# 6V_Supply.net
KiCad netlist of a schematic drawn in Altium Designer
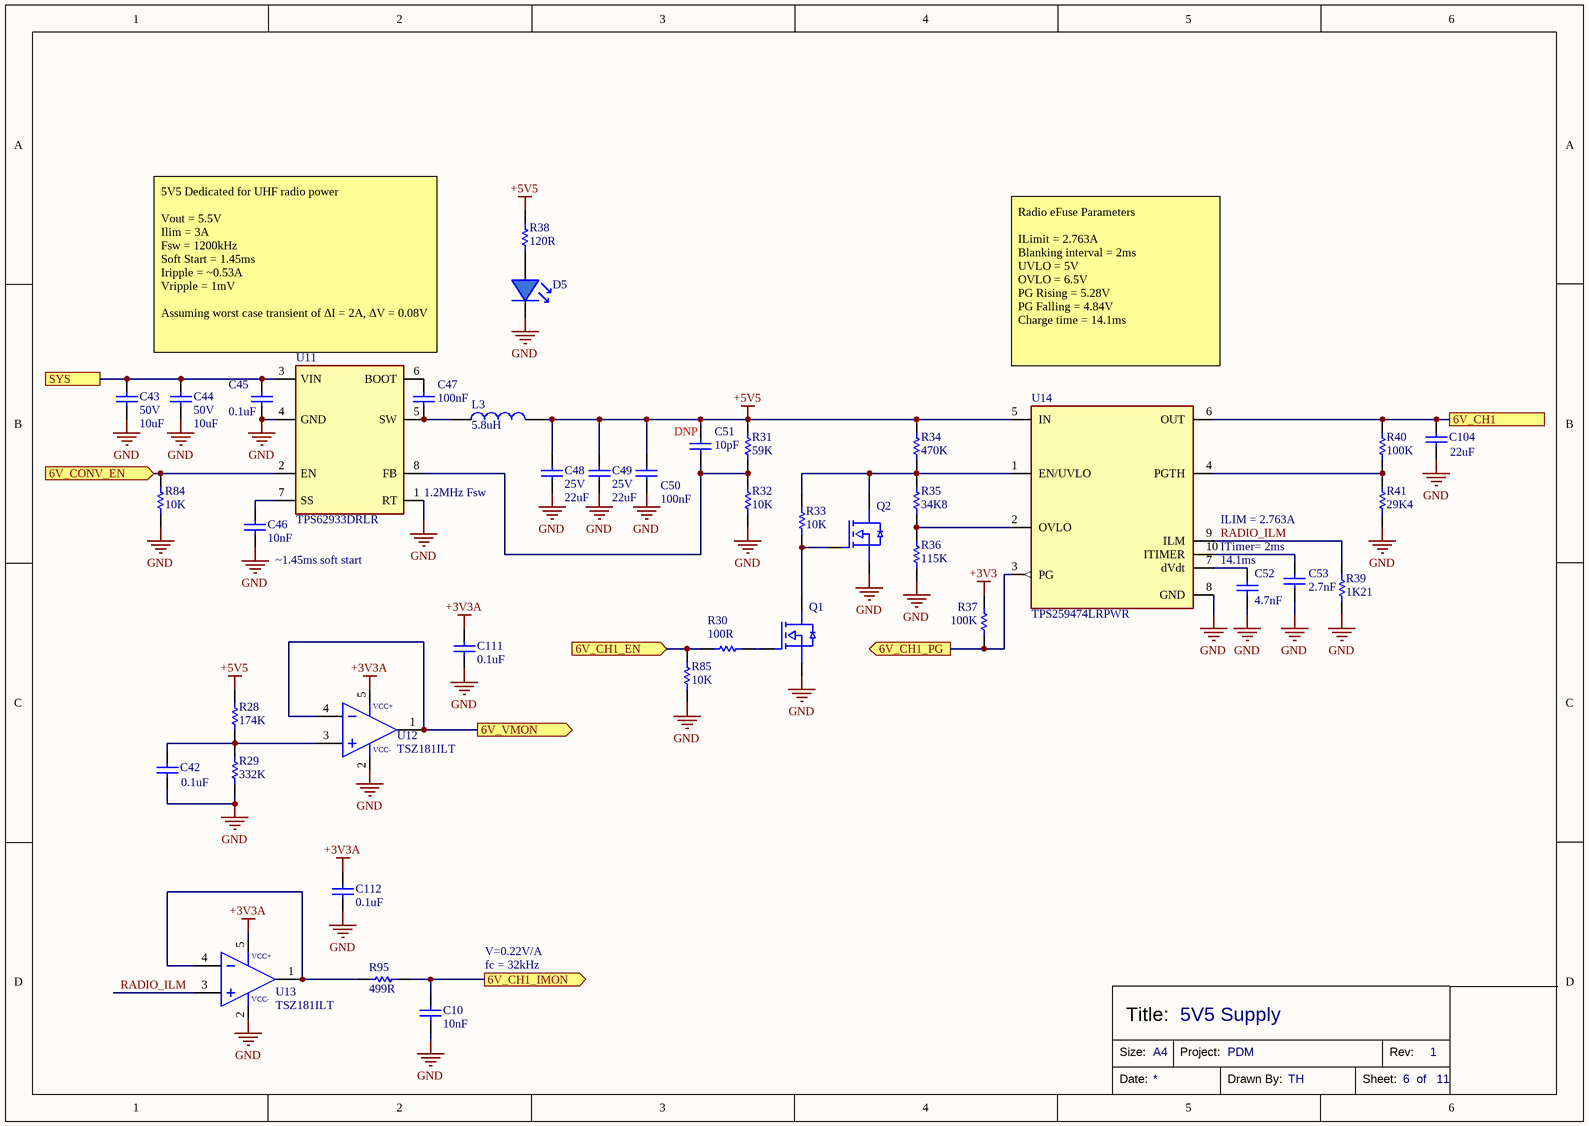
[diagram p0: 6V_Supply.SchDoc]

(export (version "E")
  (design (tool "Eeschema 10.0.6"))
  (components
    (comp (ref "C10")
      (value "CL21B103KBANNNC")
      (footprint "CAPC0805X060")
      (description "10nF ±10% 50V Ceramic Capacitor X7R 0805 (2012 Metric)")
      (fields
        (field (name "DISTRIBUTOR PART NUMBER") "1276-1015-1-ND")
        (field (name "TOLERANCE") "10%")
        (field (name "CAPACITANCE") "10nF")
      )
      (libsource (lib "Ahristi_Library") (part "CL21B103KBANNNC"))
    )
    (comp (ref "C42")
      (value "CL21B104KACNNNC")
      (footprint "CAPC0805X060")
      (description "0.1uF ±10% 25V Ceramic Capacitor X7R 0805 (2012 Metric)")
      (fields
        (field (name "DISTRIBUTOR PART NUMBER") "1276-1099-1-ND")
        (field (name "TOLERANCE") "10%")
        (field (name "CAPACITANCE") "0.1uF")
      )
      (libsource (lib "Ahristi_Library") (part "CL21B104KACNNNC"))
    )
    (comp (ref "C43")
      (value "CL32B106KBJNNNE")
      (footprint "CAPC1210X090")
      (description "10 µF ±10% 50V Ceramic Capacitor X7R 1210 (3225 Metric)")
      (fields
        (field (name "DISTRIBUTOR PART NUMBER") "1276-3387-1-ND")
        (field (name "TOLERANCE") "10%")
        (field (name "VOLTAGE RATING") "50V")
        (field (name "CAPACITANCE") "10uF")
      )
      (libsource (lib "Ahristi_Library") (part "CL32B106KBJNNNE"))
    )
    (comp (ref "C44")
      (value "CL32B106KBJNNNE")
      (footprint "CAPC1210X090")
      (description "10 µF ±10% 50V Ceramic Capacitor X7R 1210 (3225 Metric)")
      (fields
        (field (name "DISTRIBUTOR PART NUMBER") "1276-3387-1-ND")
        (field (name "TOLERANCE") "10%")
        (field (name "VOLTAGE RATING") "50V")
        (field (name "CAPACITANCE") "10uF")
      )
      (libsource (lib "Ahristi_Library") (part "CL32B106KBJNNNE"))
    )
    (comp (ref "C45")
      (value "CL05B104KB5NNNC")
      (footprint "CAPC0402X020")
      (description "0.1 µF ±10% 50V Ceramic Capacitor X7R 0402 (1005 Metric)")
      (fields
        (field (name "TOLERANCE") "10%")
        (field (name "DISTRIBUTOR PART NUMBER") "1276-CL05B104KB5NNNCCT-ND")
        (field (name "CAPACITANCE") "0.1uF")
      )
      (libsource (lib "Ahristi_Library") (part "CL05B104KB5NNNC"))
    )
    (comp (ref "C46")
      (value "CL21B103KBANNNC")
      (footprint "CAPC0805X060")
      (description "10nF ±10% 50V Ceramic Capacitor X7R 0805 (2012 Metric)")
      (fields
        (field (name "DISTRIBUTOR PART NUMBER") "1276-1015-1-ND")
        (field (name "TOLERANCE") "10%")
        (field (name "CAPACITANCE") "10nF")
      )
      (libsource (lib "Ahristi_Library") (part "CL21B103KBANNNC"))
    )
    (comp (ref "C47")
      (value "C0603C104K5RACTU")
      (footprint "CAPC0603X040")
      (description "0.1 µF ±10% 50V Ceramic Capacitor X7R 0603 (1608 Metric)")
      (fields
        (field (name "DISTRIBUTOR PART NUMBER") "399-C0603C104K5RACTUCT-ND")
        (field (name "TOLERANCE") "10%")
        (field (name "CAPACITANCE") "100nF")
      )
      (libsource (lib "Ahristi_Library") (part "C0603C104K5RACTU"))
    )
    (comp (ref "C48")
      (value "CL32B226KAJNNNE")
      (footprint "CAPC1210X090")
      (description "22 µF ±10% 25V Ceramic Capacitor X7R 1210 (3225 Metric)")
      (fields
        (field (name "DISTRIBUTOR PART NUMBER") "1276-3392-1-ND")
        (field (name "TOLERANCE") "10%")
        (field (name "VOLTAGE RATING") "25V")
        (field (name "CAPACITANCE") "22uF")
      )
      (libsource (lib "Ahristi_Library") (part "CL32B226KAJNNNE"))
    )
    (comp (ref "C49")
      (value "CL32B226KAJNNNE")
      (footprint "CAPC1210X090")
      (description "22 µF ±10% 25V Ceramic Capacitor X7R 1210 (3225 Metric)")
      (fields
        (field (name "DISTRIBUTOR PART NUMBER") "1276-3392-1-ND")
        (field (name "TOLERANCE") "10%")
        (field (name "VOLTAGE RATING") "25V")
        (field (name "CAPACITANCE") "22uF")
      )
      (libsource (lib "Ahristi_Library") (part "CL32B226KAJNNNE"))
    )
    (comp (ref "C50")
      (value "C0603C104K5RACTU")
      (footprint "CAPC0603X040")
      (description "0.1 µF ±10% 50V Ceramic Capacitor X7R 0603 (1608 Metric)")
      (fields
        (field (name "DISTRIBUTOR PART NUMBER") "399-C0603C104K5RACTUCT-ND")
        (field (name "TOLERANCE") "10%")
        (field (name "CAPACITANCE") "100nF")
      )
      (libsource (lib "Ahristi_Library") (part "C0603C104K5RACTU"))
    )
    (comp (ref "C51")
      (value "C0603C104K5RACTU")
      (footprint "CAPC0603X040")
      (description "10 pF ±5% 50V Ceramic Capacitor C0G, NP0 0603 (1608 Metric)")
      (fields
        (field (name "PART NUMBER") "C0603C100J5GACTU")
        (field (name "DISTRIBUTOR PART NUMBER") "399-C0603C100J5GACTUCT-ND")
        (field (name "CAPACITANCE") "10pF")
      )
      (libsource (lib "Ahristi_Library") (part "C0603C100J5GACTU"))
    )
    (comp (ref "C52")
      (value "CL21B105KAFNNNE")
      (footprint "CAPC0805X060")
      (description "4.7nF ±10% 50V Ceramic Capacitor X7R 0805 (2012 Metric)")
      (fields
        (field (name "PART NUMBER") "CL21B472KBANNNC")
        (field (name "DISTRIBUTOR PART NUMBER") "1276-1155-1-ND")
        (field (name "CAPACITANCE") "4.7nF")
      )
      (libsource (lib "Ahristi_Library") (part "CL21B472KBANNNC"))
    )
    (comp (ref "C53")
      (value "GRM2165C1H272JA01D")
      (footprint "CAPC0805X060")
      (description "2.7nF ±5% 50V Ceramic Capacitor C0G, NP0 0805 (2012 Metric)")
      (fields
        (field (name "DISTRIBUTOR PART NUMBER") "490-1630-1-ND")
        (field (name "TOLERANCE") "5%")
        (field (name "CAPACITANCE") "2.7nF")
      )
      (libsource (lib "Ahristi_Library") (part "GRM2165C1H272JA01D"))
    )
    (comp (ref "C104")
      (value "CL32B226MOJNNNE")
      (footprint "CAPC1210X090")
      (description "22 µF ±20% 16V Ceramic Capacitor X7R 1210 (3225 Metric)")
      (fields
        (field (name "DISTRIBUTOR PART NUMBER") "1276-3395-1-ND")
        (field (name "TOLERANCE") "10%")
        (field (name "CAPACITANCE") "22uF")
      )
      (libsource (lib "Ahristi_Library") (part "CL32B226MOJNNNE"))
    )
    (comp (ref "C111")
      (value "C0603C104K5RACTU")
      (footprint "CAPC0603X040")
      (description "0.1 µF ±10% 50V Ceramic Capacitor X7R 0603 (1608 Metric)")
      (fields
        (field (name "DISTRIBUTOR PART NUMBER") "399-C0603C104K5RACTUCT-ND")
        (field (name "TOLERANCE") "10%")
        (field (name "CAPACITANCE") "0.1uF")
      )
      (libsource (lib "Ahristi_Library") (part "C0603C104K5RACTU"))
    )
    (comp (ref "C112")
      (value "C0603C104K5RACTU")
      (footprint "CAPC0603X040")
      (description "0.1 µF ±10% 50V Ceramic Capacitor X7R 0603 (1608 Metric)")
      (fields
        (field (name "DISTRIBUTOR PART NUMBER") "399-C0603C104K5RACTUCT-ND")
        (field (name "TOLERANCE") "10%")
        (field (name "CAPACITANCE") "0.1uF")
      )
      (libsource (lib "Ahristi_Library") (part "C0603C104K5RACTU"))
    )
    (comp (ref "D5")
      (value "LSM0805463V")
      (footprint "LEDB_0805")
      (description "Blue 469nm LED Indication - Discrete 3V 0805 (2012 Metric)")
      (fields (field (name "DISTRIBUTOR PART NUMBER") "28-LSM0805463VCT-ND"))
      (libsource (lib "Ahristi_Library") (part "LEDB0805"))
    )
    (comp (ref "L3")
      (value "744316560")
      (footprint "744316560")
      (description "Inductor 5.6uH 4.5A Shielded 28.5mOhm SMD")
      (fields (field (name "DISTRIBUTOR PART NUMBER") "732-6183-1-ND"))
      (libsource (lib "Ahristi_Library") (part "744316560"))
    )
    (comp (ref "Q1")
      (value "T2N7002AK,LM")
      (footprint "SOT23-3 MOSFET")
      (description "N-Channel 60 V 200mA (Ta) 320mW (Ta) Surface Mount SOT-23-3")
      (fields (field (name "DISTRIBUTOR PART NUMBER") "T2N7002AKLMCT-ND"))
      (libsource (lib "Ahristi_Library") (part "T2N7002AK,LM"))
    )
    (comp (ref "Q2")
      (value "T2N7002AK,LM")
      (footprint "SOT23-3 MOSFET")
      (description "N-Channel 60 V 200mA (Ta) 320mW (Ta) Surface Mount SOT-23-3")
      (fields (field (name "DISTRIBUTOR PART NUMBER") "T2N7002AKLMCT-ND"))
      (libsource (lib "Ahristi_Library") (part "T2N7002AK,LM"))
    )
    (comp (ref "R28")
      (value "RMCF0603FT174K")
      (footprint "RESC0603")
      (description "174 kOhms ±1% 0.1W, 1/10W Chip Resistor 0603 (1608 Metric) Automotive AEC-Q200 Thick Film")
      (fields
        (field (name "TOLERANCE") "1%")
        (field (name "DISTRIBUTOR PART NUMBER") "RMCF0603FT174KCT-ND")
        (field (name "RESISTANCE") "174K")
      )
      (libsource (lib "Ahristi_Library") (part "RMCF0603FT174K"))
    )
    (comp (ref "R29")
      (value "RMCF0805FT332K")
      (footprint "RESC0805")
      (description "332 kOhms ±1% 0.125W, 1/8W Chip Resistor 0805 (2012 Metric) Automotive AEC-Q200 Thick Film")
      (fields
        (field (name "TOLERANCE") "1%")
        (field (name "DISTRIBUTOR PART NUMBER") "RMCF0805FT332KCT-ND")
        (field (name "RESISTANCE") "332K")
      )
      (libsource (lib "Ahristi_Library") (part "RMCF0805FT332K"))
    )
    (comp (ref "R30")
      (value "RMCF0805FT100R")
      (footprint "RESC0805")
      (description "100 Ohms ±1% 0.125W, 1/8W Chip Resistor 0805 (2012 Metric) Automotive AEC-Q200 Thick Film")
      (fields
        (field (name "TOLERANCE") "1%")
        (field (name "DISTRIBUTOR PART NUMBER") "RMCF0805FT100RCT-ND")
        (field (name "RESISTANCE") "100R")
      )
      (libsource (lib "Ahristi_Library") (part "RMCF0805FT100R"))
    )
    (comp (ref "R31")
      (value "RMCF0603FT59K0")
      (footprint "RESC0603")
      (description "59 kOhms ±1% 0.1W, 1/10W Chip Resistor 0603 (1608 Metric) Automotive AEC-Q200 Thick Film")
      (fields
        (field (name "TOLERANCE") "1%")
        (field (name "DISTRIBUTOR PART NUMBER") "RMCF0603FT59K0CT-ND")
        (field (name "RESISTANCE") "59K")
      )
      (libsource (lib "Ahristi_Library") (part "RMCF0603FT59K0"))
    )
    (comp (ref "R32")
      (value "RMCF0603FT10K0")
      (footprint "RESC0603")
      (description "10 kOhms ±1% 0.1W, 1/10W Chip Resistor 0603 (1608 Metric) Automotive AEC-Q200 Thick Film")
      (fields
        (field (name "TOLERANCE") "1%")
        (field (name "DISTRIBUTOR PART NUMBER") "RMCF0603FT10K0CT-ND")
        (field (name "RESISTANCE") "10K")
      )
      (libsource (lib "Ahristi_Library") (part "RMCF0603FT10K0"))
    )
    (comp (ref "R33")
      (value "RMCF0805FT10K0")
      (footprint "RESC0805")
      (description "10 kOhms ±1% 0.125W, 1/8W Chip Resistor 0805 (2012 Metric) Automotive AEC-Q200 Thick Film")
      (fields
        (field (name "TOLERANCE") "1%")
        (field (name "DISTRIBUTOR PART NUMBER") "RMCF0805FT10K0CT-ND")
        (field (name "RESISTANCE") "10K")
      )
      (libsource (lib "Ahristi_Library") (part "RMCF0805FT10K0"))
    )
    (comp (ref "R34")
      (value "RMCF0603FT470K")
      (footprint "RESC0603")
      (description "470 kOhms ±1% 0.1W, 1/10W Chip Resistor 0603 (1608 Metric) Automotive AEC-Q200 Thick Film")
      (fields
        (field (name "TOLERANCE") "1%")
        (field (name "DISTRIBUTOR PART NUMBER") "RMCF0603FT470KCT-ND")
        (field (name "RESISTANCE") "470K")
      )
      (libsource (lib "Ahristi_Library") (part "RMCF0603FT470K"))
    )
    (comp (ref "R35")
      (value "RMCF0805FT34K8")
      (footprint "RESC0805")
      (description "34.8 kOhms ±1% 0.125W, 1/8W Chip Resistor 0805 (2012 Metric) Automotive AEC-Q200 Thick Film")
      (fields
        (field (name "TOLERANCE") "1%")
        (field (name "DISTRIBUTOR PART NUMBER") "RMCF0805FT34K8CT-ND")
        (field (name "RESISTANCE") "34K8")
      )
      (libsource (lib "Ahristi_Library") (part "RMCF0805FT34K8"))
    )
    (comp (ref "R36")
      (value "RMCF0805FT115K")
      (footprint "RESC0805")
      (description "115 kOhms ±1% 0.125W, 1/8W Chip Resistor 0805 (2012 Metric) Automotive AEC-Q200 Thick Film")
      (fields
        (field (name "TOLERANCE") "1%")
        (field (name "DISTRIBUTOR PART NUMBER") "RMCF0805FT115KCT-ND")
        (field (name "RESISTANCE") "115K")
      )
      (libsource (lib "Ahristi_Library") (part "RMCF0805FT115K"))
    )
    (comp (ref "R37")
      (value "RMCF0805FG100K")
      (footprint "RESC0805")
      (description "100 kOhms ±1% 0.125W, 1/8W Chip Resistor 0805 (2012 Metric) Automotive AEC-Q200 Thick Film")
      (fields
        (field (name "TOLERANCE") "1%")
        (field (name "DISTRIBUTOR PART NUMBER") "RMCF0805FG100KCT-ND")
        (field (name "RESISTANCE") "100K")
      )
      (libsource (lib "Ahristi_Library") (part "RMCF0805FG100K"))
    )
    (comp (ref "R38")
      (value "RMCF0805FT120R")
      (footprint "RESC0805")
      (description "120 Ohms ±1% 0.125W, 1/8W Chip Resistor 0805 (2012 Metric) Automotive AEC-Q200 Thick Film")
      (fields
        (field (name "TOLERANCE") "1%")
        (field (name "DISTRIBUTOR PART NUMBER") "738-RMCF0805FT120RCT-ND")
        (field (name "RESISTANCE") "120R")
      )
      (libsource (lib "Ahristi_Library") (part "RMCF0805FT120R"))
    )
    (comp (ref "R39")
      (value "RMCF0805FT1K21")
      (footprint "RESC0805")
      (description "1.21 kOhms ±1% 0.125W, 1/8W Chip Resistor 0805 (2012 Metric) Automotive AEC-Q200 Thick Film")
      (fields
        (field (name "TOLERANCE") "1%")
        (field (name "DISTRIBUTOR PART NUMBER") "RMCF0805FT1K21CT-ND")
        (field (name "RESISTANCE") "1K21")
      )
      (libsource (lib "Ahristi_Library") (part "RMCF0805FT1K21"))
    )
    (comp (ref "R40")
      (value "RMCF0805FG100K")
      (footprint "RESC0805")
      (description "100 kOhms ±1% 0.125W, 1/8W Chip Resistor 0805 (2012 Metric) Automotive AEC-Q200 Thick Film")
      (fields
        (field (name "TOLERANCE") "1%")
        (field (name "DISTRIBUTOR PART NUMBER") "RMCF0805FG100KCT-ND")
        (field (name "RESISTANCE") "100K")
      )
      (libsource (lib "Ahristi_Library") (part "RMCF0805FG100K"))
    )
    (comp (ref "R41")
      (value "RMCF0805FT29K4")
      (footprint "RESC0805")
      (description "29.4 kOhms ±1% 0.125W, 1/8W Chip Resistor 0805 (2012 Metric) Automotive AEC-Q200 Thick Film")
      (fields
        (field (name "TOLERANCE") "1%")
        (field (name "DISTRIBUTOR PART NUMBER") "RMCF0805FT29K4CT-ND")
        (field (name "RESISTANCE") "29K4")
      )
      (libsource (lib "Ahristi_Library") (part "RMCF0805FT29K4"))
    )
    (comp (ref "R84")
      (value "RMCF0805FT10K0")
      (footprint "RESC0805")
      (description "10 kOhms ±1% 0.125W, 1/8W Chip Resistor 0805 (2012 Metric) Automotive AEC-Q200 Thick Film")
      (fields
        (field (name "TOLERANCE") "1%")
        (field (name "DISTRIBUTOR PART NUMBER") "RMCF0805FT10K0CT-ND")
        (field (name "RESISTANCE") "10K")
      )
      (libsource (lib "Ahristi_Library") (part "RMCF0805FT10K0"))
    )
    (comp (ref "R85")
      (value "RMCF0805FT10K0")
      (footprint "RESC0805")
      (description "10 kOhms ±1% 0.125W, 1/8W Chip Resistor 0805 (2012 Metric) Automotive AEC-Q200 Thick Film")
      (fields
        (field (name "TOLERANCE") "1%")
        (field (name "DISTRIBUTOR PART NUMBER") "RMCF0805FT10K0CT-ND")
        (field (name "RESISTANCE") "10K")
      )
      (libsource (lib "Ahristi_Library") (part "RMCF0805FT10K0"))
    )
    (comp (ref "R95")
      (value "RMCF0805FT499R")
      (footprint "RESC0805")
      (description "499 Ohms ±1% 0.125W, 1/8W Chip Resistor 0805 (2012 Metric) Automotive AEC-Q200 Thick Film")
      (fields
        (field (name "TOLERANCE") "1%")
        (field (name "DISTRIBUTOR PART NUMBER") "RMCF0805FT499RCT-ND")
        (field (name "RESISTANCE") "499R")
      )
      (libsource (lib "Ahristi_Library") (part "RMCF0805FT499R"))
    )
    (comp (ref "U11")
      (value "TPS62933DRLR")
      (footprint "SOT-583")
      (description "Buck Switching Regulator IC Positive Adjustable 0.8V 1 Output 3A SOT-583")
      (fields (field (name "DISTRIBUTOR PART NUMBER") "296-TPS62933DRLRCT-ND"))
      (libsource (lib "Ahristi_Library") (part "TPS62933DRLR"))
    )
    (comp (ref "U12")
      (value "TSZ181ILT")
      (footprint "SOT23-5 IC")
      (description "Operational Amplifier, General Purpose, 2.2V~5.5V")
      (fields (field (name "DISTRIBUTOR PART NUMBER") "497-18084-1-ND"))
      (libsource (lib "Ahristi_Library") (part "TSZ181ILT"))
    )
    (comp (ref "U13")
      (value "TSZ181ILT")
      (footprint "SOT23-5 IC")
      (description "Operational Amplifier, General Purpose, 2.2V~5.5V")
      (fields (field (name "DISTRIBUTOR PART NUMBER") "497-18084-1-ND"))
      (libsource (lib "Ahristi_Library") (part "TSZ181ILT"))
    )
    (comp (ref "U14")
      (value "TPS259474LRPWR")
      (footprint "VFQFN-10")
      (description "eFuse 5.5A, 2.7V~23V, 28mOhm, Reverse Current Blocking with Input Reverse Polarity Protection")
      (fields (field (name "DISTRIBUTOR PART NUMBER") "296-TPS259474LRPWRCT-ND"))
      (libsource (lib "Ahristi_Library") (part "TPS259474LRPWR"))
    )
  )
  (nets
    (net (code "1") (name "+3V3") (class "Default")
      (node (ref "R37") (pin "2") (pinfunction "2_2") (pintype "passive"))
    )
    (net (code "2") (name "+3V3A") (class "Default")
      (node (ref "C111") (pin "2") (pinfunction "2_2") (pintype "passive"))
      (node (ref "C112") (pin "2") (pinfunction "2_2") (pintype "passive"))
      (node (ref "U12") (pin "5") (pinfunction "VCC+_5") (pintype "power_in"))
      (node (ref "U13") (pin "5") (pinfunction "VCC+_5") (pintype "power_in"))
    )
    (net (code "3") (name "+5V5") (class "Default")
      (node (ref "C48") (pin "2") (pinfunction "2_2") (pintype "passive"))
      (node (ref "C49") (pin "2") (pinfunction "2_2") (pintype "passive"))
      (node (ref "C50") (pin "2") (pinfunction "2_2") (pintype "passive"))
      (node (ref "C51") (pin "2") (pinfunction "2_2") (pintype "passive"))
      (node (ref "L3") (pin "2") (pinfunction "2_2") (pintype "passive"))
      (node (ref "R28") (pin "2") (pinfunction "2_2") (pintype "passive"))
      (node (ref "R31") (pin "2") (pinfunction "2_2") (pintype "passive"))
      (node (ref "R34") (pin "2") (pinfunction "2_2") (pintype "passive"))
      (node (ref "R38") (pin "2") (pinfunction "2_2") (pintype "passive"))
      (node (ref "U14") (pin "5") (pinfunction "IN_5") (pintype "passive"))
    )
    (net (code "4") (name "/6V_CH1") (class "Default")
      (node (ref "C104") (pin "2") (pinfunction "2_2") (pintype "passive"))
      (node (ref "R40") (pin "2") (pinfunction "2_2") (pintype "passive"))
      (node (ref "U14") (pin "6") (pinfunction "OUT_6") (pintype "passive"))
    )
    (net (code "5") (name "/6V_CH1_EN") (class "Default")
      (node (ref "R30") (pin "2") (pinfunction "2_2") (pintype "passive"))
      (node (ref "R85") (pin "2") (pinfunction "2_2") (pintype "passive"))
    )
    (net (code "6") (name "/6V_CH1_IMON") (class "Default")
      (node (ref "C10") (pin "2") (pinfunction "2_2") (pintype "passive"))
      (node (ref "R95") (pin "2") (pinfunction "2_2") (pintype "passive"))
    )
    (net (code "7") (name "/6V_CH1_PG") (class "Default")
      (node (ref "R37") (pin "1") (pinfunction "1_1") (pintype "passive"))
      (node (ref "U14") (pin "3") (pinfunction "PG_3") (pintype "output"))
    )
    (net (code "8") (name "/6V_CONV_EN") (class "Default")
      (node (ref "R84") (pin "2") (pinfunction "2_2") (pintype "passive"))
      (node (ref "U11") (pin "2") (pinfunction "EN_2") (pintype "passive"))
    )
    (net (code "9") (name "/6V_VMON") (class "Default")
      (node (ref "U12") (pin "1") (pinfunction "OUT_1") (pintype "passive"))
      (node (ref "U12") (pin "4") (pinfunction "IN-_4") (pintype "passive"))
    )
    (net (code "10") (name "/RADIO_ILM") (class "Default")
      (node (ref "R39") (pin "2") (pinfunction "2_2") (pintype "passive"))
      (node (ref "U13") (pin "3") (pinfunction "IN+_3") (pintype "passive"))
      (node (ref "U14") (pin "9") (pinfunction "ILM_9") (pintype "passive"))
    )
    (net (code "11") (name "/SYS") (class "Default")
      (node (ref "C43") (pin "2") (pinfunction "2_2") (pintype "passive"))
      (node (ref "C44") (pin "2") (pinfunction "2_2") (pintype "passive"))
      (node (ref "C45") (pin "2") (pinfunction "2_2") (pintype "passive"))
      (node (ref "U11") (pin "3") (pinfunction "VIN_3") (pintype "passive"))
    )
    (net (code "12") (name "GND") (class "Default")
      (node (ref "C10") (pin "1") (pinfunction "1_1") (pintype "passive"))
      (node (ref "C104") (pin "1") (pinfunction "1_1") (pintype "passive"))
      (node (ref "C111") (pin "1") (pinfunction "1_1") (pintype "passive"))
      (node (ref "C112") (pin "1") (pinfunction "1_1") (pintype "passive"))
      (node (ref "C42") (pin "1") (pinfunction "1_1") (pintype "passive"))
      (node (ref "C43") (pin "1") (pinfunction "1_1") (pintype "passive"))
      (node (ref "C44") (pin "1") (pinfunction "1_1") (pintype "passive"))
      (node (ref "C45") (pin "1") (pinfunction "1_1") (pintype "passive"))
      (node (ref "C46") (pin "1") (pinfunction "1_1") (pintype "passive"))
      (node (ref "C48") (pin "1") (pinfunction "1_1") (pintype "passive"))
      (node (ref "C49") (pin "1") (pinfunction "1_1") (pintype "passive"))
      (node (ref "C50") (pin "1") (pinfunction "1_1") (pintype "passive"))
      (node (ref "C52") (pin "1") (pinfunction "1_1") (pintype "passive"))
      (node (ref "C53") (pin "1") (pinfunction "1_1") (pintype "passive"))
      (node (ref "D5") (pin "K") (pinfunction "K_K") (pintype "passive"))
      (node (ref "Q1") (pin "S") (pinfunction "S_S") (pintype "passive"))
      (node (ref "Q2") (pin "S") (pinfunction "S_S") (pintype "passive"))
      (node (ref "R29") (pin "1") (pinfunction "1_1") (pintype "passive"))
      (node (ref "R32") (pin "1") (pinfunction "1_1") (pintype "passive"))
      (node (ref "R36") (pin "1") (pinfunction "1_1") (pintype "passive"))
      (node (ref "R39") (pin "1") (pinfunction "1_1") (pintype "passive"))
      (node (ref "R41") (pin "1") (pinfunction "1_1") (pintype "passive"))
      (node (ref "R84") (pin "1") (pinfunction "1_1") (pintype "passive"))
      (node (ref "R85") (pin "1") (pinfunction "1_1") (pintype "passive"))
      (node (ref "U11") (pin "1") (pinfunction "RT_1") (pintype "passive"))
      (node (ref "U11") (pin "4") (pinfunction "GND_4") (pintype "passive"))
      (node (ref "U12") (pin "2") (pinfunction "VCC-_2") (pintype "power_in"))
      (node (ref "U13") (pin "2") (pinfunction "VCC-_2") (pintype "power_in"))
      (node (ref "U14") (pin "8") (pinfunction "GND_8") (pintype "passive"))
    )
    (net (code "13") (name "Net-(D5-PadA)") (class "Default")
      (node (ref "D5") (pin "A") (pinfunction "A_A") (pintype "passive"))
      (node (ref "R38") (pin "1") (pinfunction "1_1") (pintype "passive"))
    )
    (net (code "14") (name "Net-(Q1-PadD)") (class "Default")
      (node (ref "Q1") (pin "D") (pinfunction "D_D") (pintype "passive"))
      (node (ref "Q2") (pin "G") (pinfunction "G_G") (pintype "passive"))
      (node (ref "R33") (pin "1") (pinfunction "1_1") (pintype "passive"))
    )
    (net (code "15") (name "Net-(Q1-PadG)") (class "Default")
      (node (ref "Q1") (pin "G") (pinfunction "G_G") (pintype "passive"))
      (node (ref "R30") (pin "1") (pinfunction "1_1") (pintype "passive"))
    )
    (net (code "16") (name "Net-(U11-BOOT)") (class "Default")
      (node (ref "C47") (pin "2") (pinfunction "2_2") (pintype "passive"))
      (node (ref "U11") (pin "6") (pinfunction "BOOT_6") (pintype "passive"))
    )
    (net (code "17") (name "Net-(U11-FB)") (class "Default")
      (node (ref "C51") (pin "1") (pinfunction "1_1") (pintype "passive"))
      (node (ref "R31") (pin "1") (pinfunction "1_1") (pintype "passive"))
      (node (ref "R32") (pin "2") (pinfunction "2_2") (pintype "passive"))
      (node (ref "U11") (pin "8") (pinfunction "FB_8") (pintype "passive"))
    )
    (net (code "18") (name "Net-(U11-SS)") (class "Default")
      (node (ref "C46") (pin "2") (pinfunction "2_2") (pintype "passive"))
      (node (ref "U11") (pin "7") (pinfunction "SS_7") (pintype "passive"))
    )
    (net (code "19") (name "Net-(U11-SW)") (class "Default")
      (node (ref "C47") (pin "1") (pinfunction "1_1") (pintype "passive"))
      (node (ref "L3") (pin "1") (pinfunction "1_1") (pintype "passive"))
      (node (ref "U11") (pin "5") (pinfunction "SW_5") (pintype "passive"))
    )
    (net (code "20") (name "Net-(U12-IN+)") (class "Default")
      (node (ref "C42") (pin "2") (pinfunction "2_2") (pintype "passive"))
      (node (ref "R28") (pin "1") (pinfunction "1_1") (pintype "passive"))
      (node (ref "R29") (pin "2") (pinfunction "2_2") (pintype "passive"))
      (node (ref "U12") (pin "3") (pinfunction "IN+_3") (pintype "passive"))
    )
    (net (code "21") (name "Net-(U13-IN-)") (class "Default")
      (node (ref "R95") (pin "1") (pinfunction "1_1") (pintype "passive"))
      (node (ref "U13") (pin "1") (pinfunction "OUT_1") (pintype "passive"))
      (node (ref "U13") (pin "4") (pinfunction "IN-_4") (pintype "passive"))
    )
    (net (code "22") (name "Net-(U14-EN{slash}UVLO)") (class "Default")
      (node (ref "Q2") (pin "D") (pinfunction "D_D") (pintype "passive"))
      (node (ref "R33") (pin "2") (pinfunction "2_2") (pintype "passive"))
      (node (ref "R34") (pin "1") (pinfunction "1_1") (pintype "passive"))
      (node (ref "R35") (pin "2") (pinfunction "2_2") (pintype "passive"))
      (node (ref "U14") (pin "1") (pinfunction "EN/UVLO_1") (pintype "passive"))
    )
    (net (code "23") (name "Net-(U14-ITIMER)") (class "Default")
      (node (ref "C53") (pin "2") (pinfunction "2_2") (pintype "passive"))
      (node (ref "U14") (pin "10") (pinfunction "ITIMER_10") (pintype "passive"))
    )
    (net (code "24") (name "Net-(U14-OVLO)") (class "Default")
      (node (ref "R35") (pin "1") (pinfunction "1_1") (pintype "passive"))
      (node (ref "R36") (pin "2") (pinfunction "2_2") (pintype "passive"))
      (node (ref "U14") (pin "2") (pinfunction "OVLO_2") (pintype "passive"))
    )
    (net (code "25") (name "Net-(U14-PGTH)") (class "Default")
      (node (ref "R40") (pin "1") (pinfunction "1_1") (pintype "passive"))
      (node (ref "R41") (pin "2") (pinfunction "2_2") (pintype "passive"))
      (node (ref "U14") (pin "4") (pinfunction "PGTH_4") (pintype "passive"))
    )
    (net (code "26") (name "Net-(U14-dVdt)") (class "Default")
      (node (ref "C52") (pin "2") (pinfunction "2_2") (pintype "passive"))
      (node (ref "U14") (pin "7") (pinfunction "dVdt_7") (pintype "passive"))
    )
  )
)
